# Sheet1.net
KiCad netlist of a schematic drawn in Altium Designer
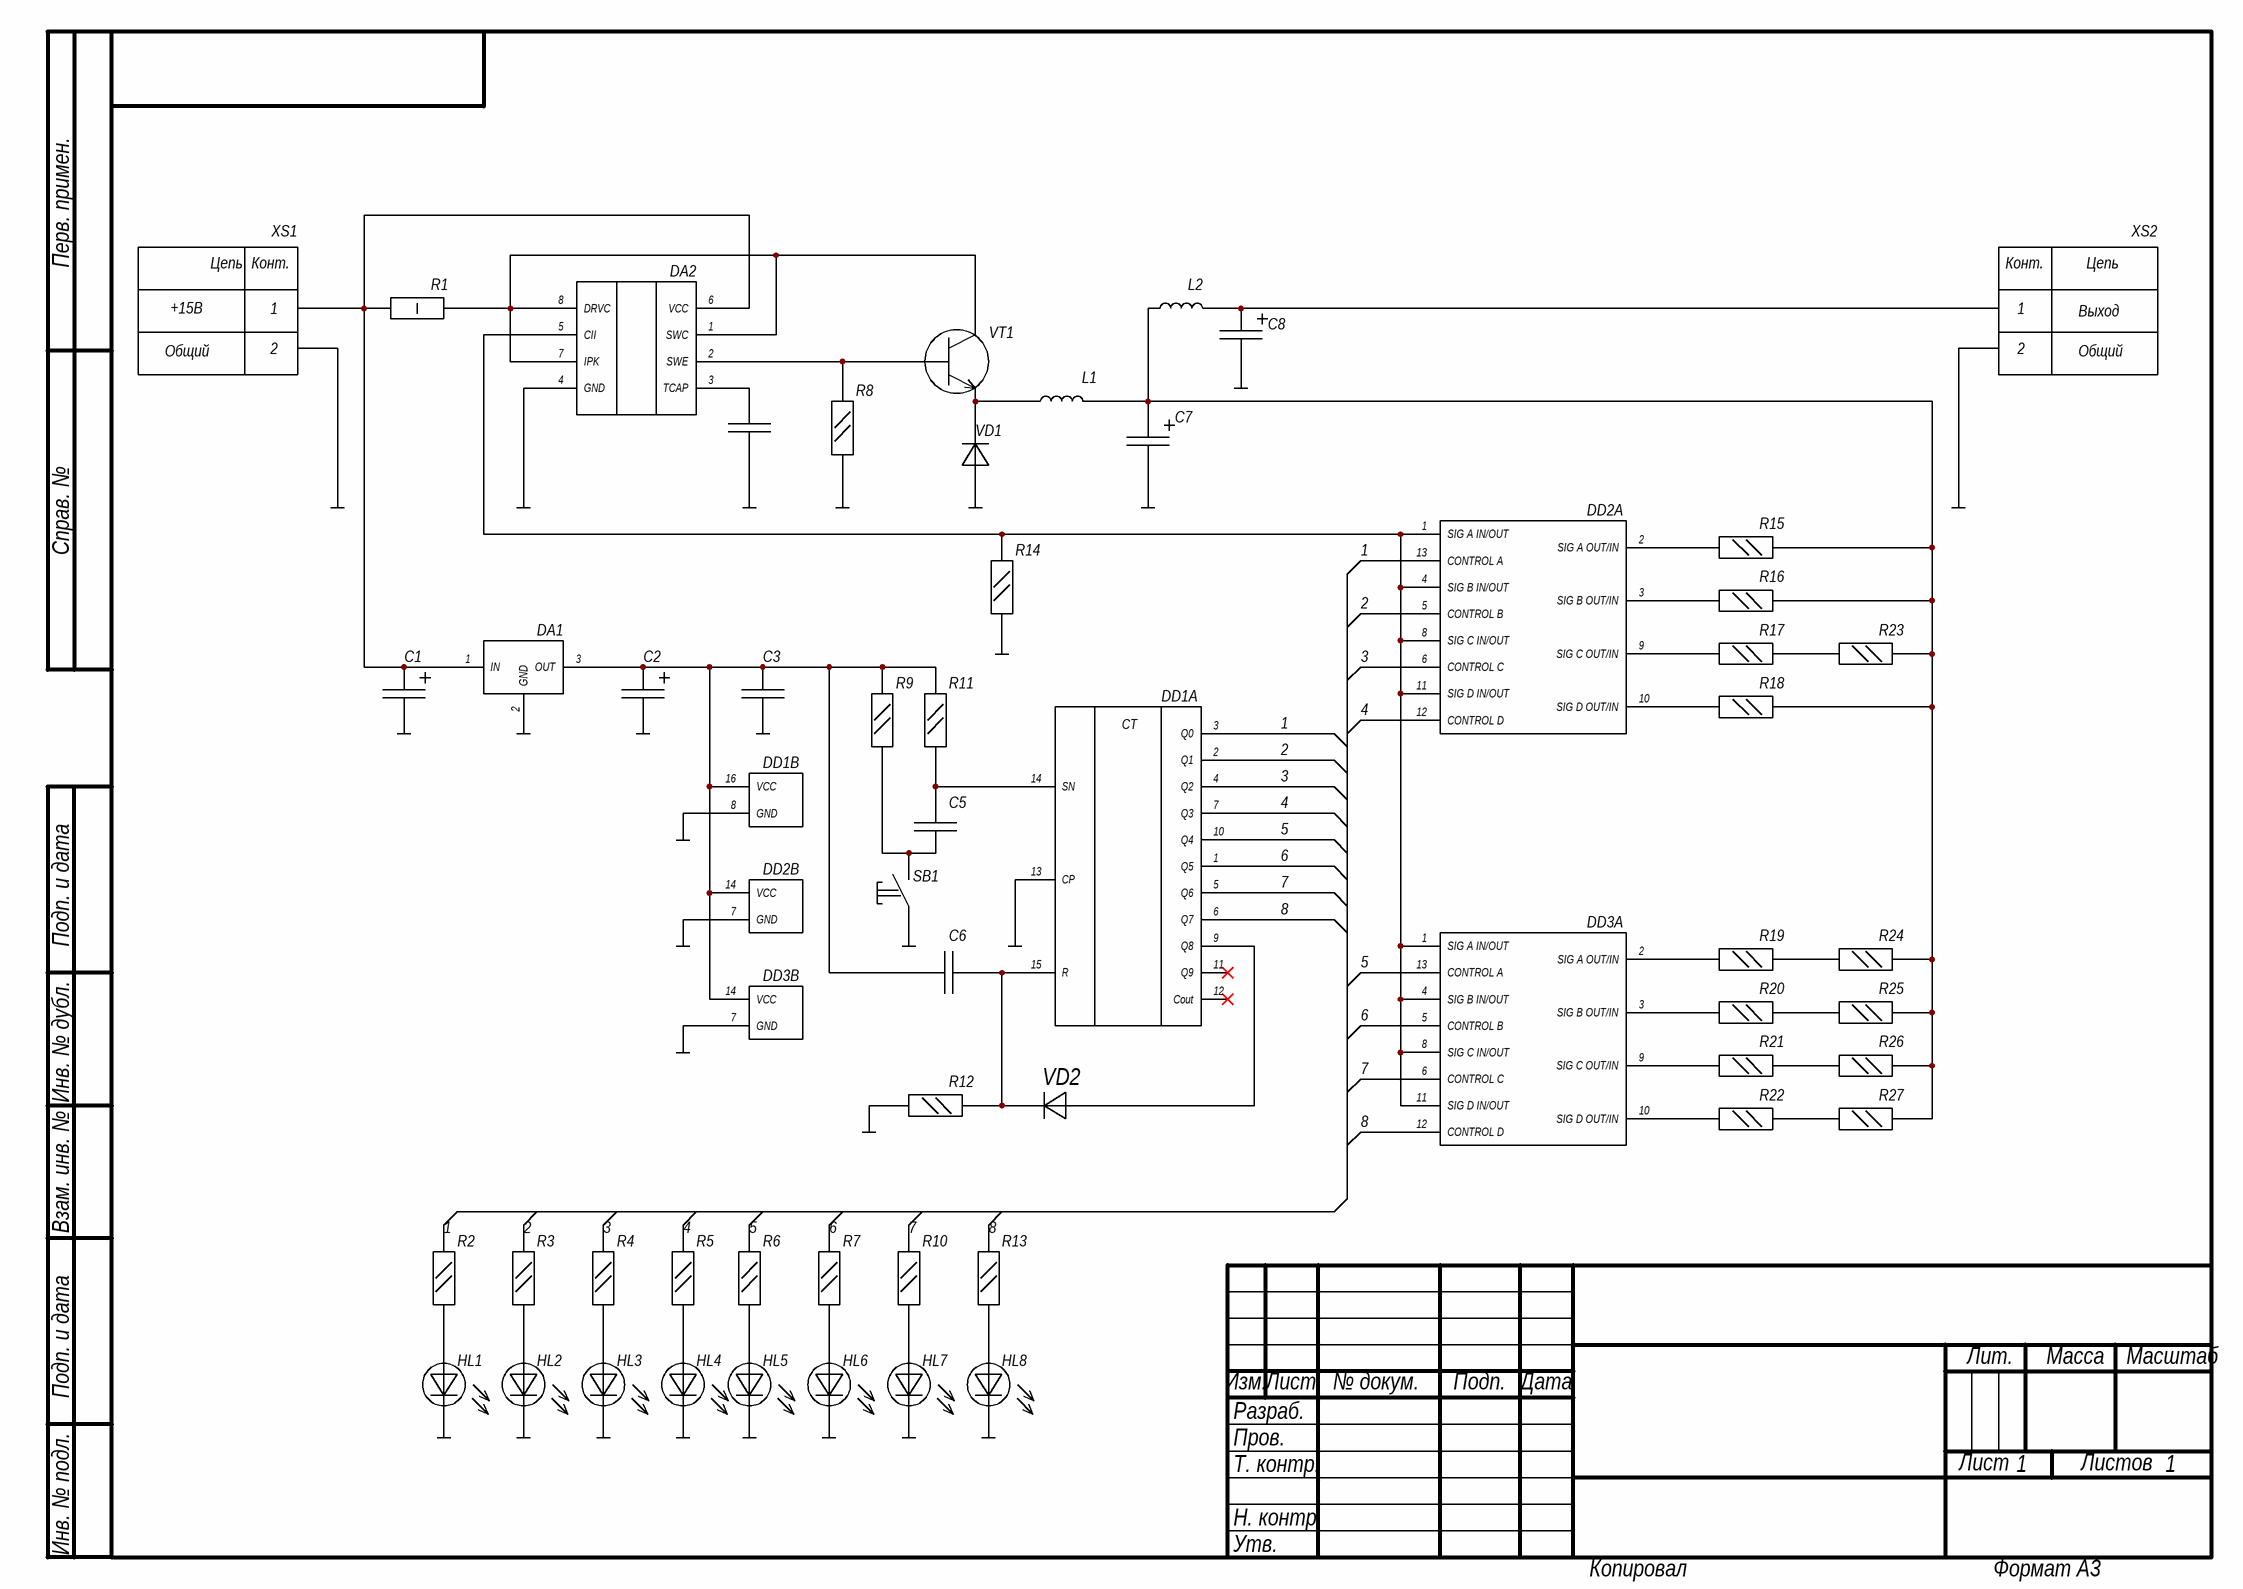
[diagram p0: Sheet1.SchDoc]

(export (version "E")
  (design (tool "Eeschema 10.0.6"))
  (components
    (comp (ref "C1")
      (value "100uF 25V")
      (footprint "CAPPR250-630X1120")
      (description "ECAP TKR101M1EE11 25В 100мкФ ±5% (Jamicon, Китай)")
      (libsource (lib "Schlib1") (part "Cap Polarity 100uF 25V"))
    )
    (comp (ref "C2")
      (value "100uF 25V")
      (footprint "CAPPR250-630X1120")
      (description "ECAP TKR101M1EE11 25В 100мкФ ±5% (Jamicon, Китай)")
      (libsource (lib "Schlib1") (part "Cap Polarity 100uF 25V"))
    )
    (comp (ref "C3")
      (value "Cap Ceramic 0.1uF")
      (footprint "CAPPRB508-450X850")
      (description "CAP X7R RDER71H104K 25В 0.1мкФ ±10% (Murata, Япония)")
      (libsource (lib "Schlib1") (part "Cap Ceramic 0.1uF"))
    )
    (comp (ref "C4")
      (value "Cap Ceramic 470pF")
      (footprint "CAPPRB508-450X850")
      (description "CAP NPO RDE5C1H471J 25В 470пкФ ±5% (Murata, Япония)")
      (libsource (lib "Schlib1") (part "Cap Ceramic 470pF"))
    )
    (comp (ref "C5")
      (value "Cap Ceramic 0.1uF")
      (footprint "CAPPRB508-450X850")
      (description "CAP X7R RDER71H104K 25В 0.1мкФ ±10% (Murata, Япония)")
      (libsource (lib "Schlib1") (part "Cap Ceramic 0.1uF"))
    )
    (comp (ref "C6")
      (value "Cap Ceramic 0.1uF")
      (footprint "CAPPRB508-450X850")
      (description "CAP X7R RDER71H104K 25В 0.1мкФ ±10% (Murata, Япония)")
      (libsource (lib "Schlib1") (part "Cap Ceramic 0.1uF"))
    )
    (comp (ref "C7")
      (value "470uF 25V")
      (footprint "CAPPR350-850X1300")
      (description "ECAP TKR471M1EF14 25В 470мкФ ±5% (Jamicon, Китай)")
      (libsource (lib "Schlib1") (part "Cap Polarity 470uF 25V"))
    )
    (comp (ref "C8")
      (value "470uF 25V")
      (footprint "CAPPR350-850X1300")
      (description "ECAP TKR471M1EF14 25В 470мкФ ±5% (Jamicon, Китай)")
      (libsource (lib "Schlib1") (part "Cap Polarity 470uF 25V"))
    )
    (comp (ref "DA1")
      (value "L7809ABV")
      (footprint "TO-220AB")
      (description "L7809ABV (STMicroelectronics, Швейцария)")
      (libsource (lib "Schlib1") (part "L7809ABV"))
    )
    (comp (ref "DA2")
      (value "MC34063ABN")
      (footprint "DIPS8-300")
      (description "MC34063ABN (STMicroelectronis, Швейцария)")
      (libsource (lib "Schlib1") (part "MC34063ABN"))
    )
    (comp (ref "DD1")
      (value "CD4017BE")
      (footprint "DIPS16-300")
      (description "CD4017BE (Texas Instuments, США)")
      (libsource (lib "Schlib1") (part "CD4017BE"))
    )
    (comp (ref "DD2")
      (value "CD4066BE")
      (footprint "DIPS14-300")
      (description "CD4066BE (HGSEMI, Китай)")
      (libsource (lib "Schlib1") (part "CD4066BE"))
    )
    (comp (ref "DD3")
      (value "CD4066BE")
      (footprint "DIPS14-300")
      (description "CD4066BE (HGSEMI, Китай)")
      (libsource (lib "Schlib1") (part "CD4066BE"))
    )
    (comp (ref "HL1")
      (value "LED Red")
      (footprint "LD-5mm-R")
      (description "GNL-5012ED (G-nor Electronics, Китай)")
      (libsource (lib "Schlib1") (part "LED Red"))
    )
    (comp (ref "HL2")
      (value "LED Red")
      (footprint "LD-5mm-R")
      (description "GNL-5012ED (G-nor Electronics, Китай)")
      (libsource (lib "Schlib1") (part "LED Red"))
    )
    (comp (ref "HL3")
      (value "LED Red")
      (footprint "LD-5mm-R")
      (description "GNL-5012ED (G-nor Electronics, Китай)")
      (libsource (lib "Schlib1") (part "LED Red"))
    )
    (comp (ref "HL4")
      (value "LED Red")
      (footprint "LD-5mm-R")
      (description "GNL-5012ED (G-nor Electronics, Китай)")
      (libsource (lib "Schlib1") (part "LED Red"))
    )
    (comp (ref "HL5")
      (value "LED Red")
      (footprint "LD-5mm-R")
      (description "GNL-5012ED (G-nor Electronics, Китай)")
      (libsource (lib "Schlib1") (part "LED Red"))
    )
    (comp (ref "HL6")
      (value "LED Red")
      (footprint "LD-5mm-R")
      (description "GNL-5012ED (G-nor Electronics, Китай)")
      (libsource (lib "Schlib1") (part "LED Red"))
    )
    (comp (ref "HL7")
      (value "LED Red")
      (footprint "LD-5mm-R")
      (description "GNL-5012ED (G-nor Electronics, Китай)")
      (libsource (lib "Schlib1") (part "LED Red"))
    )
    (comp (ref "HL8")
      (value "LED Red")
      (footprint "LD-5mm-R")
      (description "GNL-5012ED (G-nor Electronics, Китай)")
      (libsource (lib "Schlib1") (part "LED Red"))
    )
    (comp (ref "L1")
      (value "КИ (КИГ) 3,0−100мкГн ±5%")
      (footprint "INDRD_WURTH_WE-TI")
      (description "КИ (КИГ) 3,0−100мкГн ±10% (Россия)")
      (libsource (lib "Schlib1") (part "Inductor КИ (КИГ) 3,0−100мкГн ±5%"))
    )
    (comp (ref "L2")
      (value "КИ (КИГ) 3,0−100мкГн ±5%")
      (footprint "INDRD_WURTH_WE-TI")
      (description "КИ (КИГ) 3,0−100мкГн ±10% (Россия)")
      (libsource (lib "Schlib1") (part "Inductor КИ (КИГ) 3,0−100мкГн ±5%"))
    )
    (comp (ref "R1")
      (value "0,1Ом")
      (footprint "Res 1W")
      (description "С1-4−1−0,1Ом ±5% (Россия)")
      (libsource (lib "Schlib1") (part "Res 0,1 1W"))
    )
    (comp (ref "R2")
      (value "1кОм")
      (footprint "Res 0.125W")
      (description "С1-4−0,125−1кОм ±5% (Россия)")
      (libsource (lib "Schlib1") (part "Res 1K 0.125W"))
    )
    (comp (ref "R3")
      (value "1кОм")
      (footprint "Res 0.125W")
      (description "С1-4−0,125−1кОм ±5% (Россия)")
      (libsource (lib "Schlib1") (part "Res 1K 0.125W"))
    )
    (comp (ref "R4")
      (value "1кОм")
      (footprint "Res 0.125W")
      (description "С1-4−0,125−1кОм ±5% (Россия)")
      (libsource (lib "Schlib1") (part "Res 1K 0.125W"))
    )
    (comp (ref "R5")
      (value "1кОм")
      (footprint "Res 0.125W")
      (description "С1-4−0,125−1кОм ±5% (Россия)")
      (libsource (lib "Schlib1") (part "Res 1K 0.125W"))
    )
    (comp (ref "R6")
      (value "1кОм")
      (footprint "Res 0.125W")
      (description "С1-4−0,125−1кОм ±5% (Россия)")
      (libsource (lib "Schlib1") (part "Res 1K 0.125W"))
    )
    (comp (ref "R7")
      (value "1кОм")
      (footprint "Res 0.125W")
      (description "С1-4−0,125−1кОм ±5% (Россия)")
      (libsource (lib "Schlib1") (part "Res 1K 0.125W"))
    )
    (comp (ref "R8")
      (value "22кОм")
      (footprint "Res 0.125W")
      (description "С1-4−0,125−22кОм ±5% (Россия)")
      (libsource (lib "Schlib1") (part "Res 22K 0.125W"))
    )
    (comp (ref "R9")
      (value "100кОм")
      (footprint "Res 0.125W")
      (description "С1-4−0,125−100кОм ±5% (Россия)")
      (libsource (lib "Schlib1") (part "Res 100K 0.125W"))
    )
    (comp (ref "R10")
      (value "1кОм")
      (footprint "Res 0.125W")
      (description "С1-4−0,125−1кОм ±5% (Россия)")
      (libsource (lib "Schlib1") (part "Res 1K 0.125W"))
    )
    (comp (ref "R11")
      (value "100кОм")
      (footprint "Res 0.125W")
      (description "С1-4−0,125−100кОм ±5% (Россия)")
      (libsource (lib "Schlib1") (part "Res 100K 0.125W"))
    )
    (comp (ref "R12")
      (value "100кОм")
      (footprint "Res 0.125W")
      (description "С1-4−0,125−100кОм ±5% (Россия)")
      (libsource (lib "Schlib1") (part "Res 100K 0.125W"))
    )
    (comp (ref "R13")
      (value "1кОм")
      (footprint "Res 0.125W")
      (description "С1-4−0,125−1кОм ±5% (Россия)")
      (libsource (lib "Schlib1") (part "Res 1K 0.125W"))
    )
    (comp (ref "R14")
      (value "1кОм")
      (footprint "Res 0.125W")
      (description "С1-4−0,125−1,5кОм ±5% (Россия)")
      (libsource (lib "Schlib1") (part "Res 1,5K 0.125W"))
    )
    (comp (ref "R15")
      (value "270Ом")
      (footprint "Res 0.125W")
      (description "С1-4−0,125−270Ом ±5% (Россия)")
      (libsource (lib "Schlib1") (part "Res 270 0.125W"))
    )
    (comp (ref "R16")
      (value "1кОм")
      (footprint "Res 0.125W")
      (description "С1-4−0,125−1,5кОм ±5% (Россия)")
      (libsource (lib "Schlib1") (part "Res 1,5K 0.125W"))
    )
    (comp (ref "R17")
      (value "2кОм")
      (footprint "Res 0.125W")
      (description "С1-4−0,125−2кОм ±5% (Россия)")
      (libsource (lib "Schlib1") (part "Res 2K 0.125W"))
    )
    (comp (ref "R18")
      (value "3,9кОм")
      (footprint "Res 0.125W")
      (description "С1-4−0,125−3,9кОм ±5% (Россия)")
      (libsource (lib "Schlib1") (part "Res 3,9K 0.125W"))
    )
    (comp (ref "R19")
      (value "4,3кОм")
      (footprint "Res 0.125W")
      (description "С1-4−0,125−4,3кОм ±5% (Россия)")
      (libsource (lib "Schlib1") (part "Res 4,3K 0.125W"))
    )
    (comp (ref "R20")
      (value "5,6кОм")
      (footprint "Res 0.125W")
      (description "С1-4−0,125−5,6кОм ±5% (Россия)")
      (libsource (lib "Schlib1") (part "Res 5,6K 0.125W"))
    )
    (comp (ref "R21")
      (value "7,5кОм")
      (footprint "Res 0.125W")
      (description "С1-4−0,125−7,5кОм ±5% (Россия)")
      (libsource (lib "Schlib1") (part "Res 7,5K 0.125W"))
    )
    (comp (ref "R22")
      (value "9,1кОм")
      (footprint "Res 0.125W")
      (description "С1-4−0,125−9,1кОм ±5% (Россия)")
      (libsource (lib "Schlib1") (part "Res 9,1K 0.125W"))
    )
    (comp (ref "R23")
      (value "100Ом")
      (footprint "Res 0.125W")
      (description "С1-4−0,125−100Ом ±5% (Россия)")
      (libsource (lib "Schlib1") (part "Res 100 0.125W"))
    )
    (comp (ref "R24")
      (value "200Ом")
      (footprint "Res 0.125W")
      (description "С1-4−0,125−200Ом ±5% (Россия)")
      (libsource (lib "Schlib1") (part "Res 200 0.125W"))
    )
    (comp (ref "R25")
      (value "200Ом")
      (footprint "Res 0.125W")
      (description "С1-4−0,125−200Ом ±5% (Россия)")
      (libsource (lib "Schlib1") (part "Res 200 0.125W"))
    )
    (comp (ref "R26")
      (value "100Ом")
      (footprint "Res 0.125W")
      (description "С1-4−0,125−100Ом ±5% (Россия)")
      (libsource (lib "Schlib1") (part "Res 100 0.125W"))
    )
    (comp (ref "R27")
      (value "300Ом")
      (footprint "Res 0.125W")
      (description "С1-4−0,125−300Ом ±5% (Россия)")
      (libsource (lib "Schlib1") (part "Res 300 0.125W"))
    )
    (comp (ref "SB1")
      (value "Button SMD")
      (footprint "Button SMD")
      (description "Кнопка тактовая 1437566-3 (TE Connectivity, США)")
      (libsource (lib "Schlib1") (part "Button"))
    )
    (comp (ref "VD1")
      (value "1N5820")
      (footprint "DO-27")
      (description "1N5820 (Diotec, Германия)")
      (libsource (lib "Schlib1") (part "Diode 1N5820"))
    )
    (comp (ref "VD2")
      (value "1N4002")
      (footprint "DO-35")
      (description "1N4148 (Diotec, Германия)")
      (fields (field (name "PUBLISHER") "Andrew Danich"))
      (libsource (lib "Schlib1") (part "Diode 1N4148"))
    )
    (comp (ref "VT1")
      (value "TIP121G")
      (footprint "TO-220AB")
      (description "TIP121G (ON Semiconductor, США)")
      (libsource (lib "Schlib1") (part "Transistor TIP121G"))
    )
    (comp (ref "XS1")
      (value "Power Connector 2 pin")
      (footprint "WIELAND_25.161.0253.0")
      (description "25.161.0253.0 (Wieland Electric, Германия)")
      (libsource (lib "Schlib1") (part "Power Connector 2 pin"))
    )
    (comp (ref "XS2")
      (value "Power Connector 2 pin")
      (footprint "WIELAND_25.161.0253.0")
      (description "25.161.0253.0 (Wieland Electric, Германия)")
      (libsource (lib "Schlib1") (part "Power Connector 2 pin"))
    )
  )
  (nets
    (net (code "1") (name "/1") (class "Default")
      (node (ref "DD1") (pin "3") (pinfunction "Q0_3") (pintype "passive"))
      (node (ref "DD2") (pin "13") (pinfunction "CONTROL_A_13") (pintype "passive"))
    )
    (net (code "2") (name "/2") (class "Default")
      (node (ref "DD1") (pin "2") (pinfunction "Q1_2") (pintype "passive"))
      (node (ref "DD2") (pin "5") (pinfunction "CONTROL_B_5") (pintype "passive"))
    )
    (net (code "3") (name "/3") (class "Default")
      (node (ref "DD1") (pin "4") (pinfunction "Q2_4") (pintype "passive"))
      (node (ref "DD2") (pin "6") (pinfunction "CONTROL_C_6") (pintype "passive"))
    )
    (net (code "4") (name "/4") (class "Default")
      (node (ref "DD1") (pin "7") (pinfunction "Q3_7") (pintype "passive"))
      (node (ref "DD2") (pin "12") (pinfunction "CONTROL_D_12") (pintype "passive"))
    )
    (net (code "5") (name "/5") (class "Default")
      (node (ref "DD1") (pin "10") (pinfunction "Q4_10") (pintype "passive"))
      (node (ref "DD3") (pin "13") (pinfunction "CONTROL_A_13") (pintype "passive"))
    )
    (net (code "6") (name "/6") (class "Default")
      (node (ref "DD1") (pin "1") (pinfunction "Q5_1") (pintype "passive"))
      (node (ref "DD3") (pin "5") (pinfunction "CONTROL_B_5") (pintype "passive"))
    )
    (net (code "7") (name "/7") (class "Default")
      (node (ref "DD1") (pin "5") (pinfunction "Q6_5") (pintype "passive"))
      (node (ref "DD3") (pin "6") (pinfunction "CONTROL_C_6") (pintype "passive"))
    )
    (net (code "8") (name "/8") (class "Default")
      (node (ref "DD1") (pin "6") (pinfunction "Q7_6") (pintype "passive"))
      (node (ref "DD3") (pin "12") (pinfunction "CONTROL_D_12") (pintype "passive"))
    )
    (net (code "9") (name "GND") (class "Default")
      (node (ref "C1") (pin "2") (pinfunction "2_2") (pintype "passive"))
      (node (ref "C2") (pin "2") (pinfunction "2_2") (pintype "passive"))
      (node (ref "C3") (pin "2") (pinfunction "2_2") (pintype "passive"))
      (node (ref "C4") (pin "2") (pinfunction "2_2") (pintype "passive"))
      (node (ref "C7") (pin "2") (pinfunction "2_2") (pintype "passive"))
      (node (ref "C8") (pin "2") (pinfunction "2_2") (pintype "passive"))
      (node (ref "DA1") (pin "2") (pinfunction "GND_2") (pintype "passive"))
      (node (ref "DA2") (pin "4") (pinfunction "GND_4") (pintype "passive"))
      (node (ref "DD1") (pin "13") (pinfunction "CP_13") (pintype "passive"))
      (node (ref "DD1") (pin "8") (pinfunction "GND_8") (pintype "passive"))
      (node (ref "DD2") (pin "7") (pinfunction "GND_7") (pintype "passive"))
      (node (ref "DD3") (pin "7") (pinfunction "GND_7") (pintype "passive"))
      (node (ref "HL1") (pin "2") (pinfunction "K_2") (pintype "passive"))
      (node (ref "HL2") (pin "2") (pinfunction "K_2") (pintype "passive"))
      (node (ref "HL3") (pin "2") (pinfunction "K_2") (pintype "passive"))
      (node (ref "HL4") (pin "2") (pinfunction "K_2") (pintype "passive"))
      (node (ref "HL5") (pin "2") (pinfunction "K_2") (pintype "passive"))
      (node (ref "HL6") (pin "2") (pinfunction "K_2") (pintype "passive"))
      (node (ref "HL7") (pin "2") (pinfunction "K_2") (pintype "passive"))
      (node (ref "HL8") (pin "2") (pinfunction "K_2") (pintype "passive"))
      (node (ref "R12") (pin "1") (pinfunction "1_1") (pintype "passive"))
      (node (ref "R14") (pin "1") (pinfunction "1_1") (pintype "passive"))
      (node (ref "R8") (pin "1") (pinfunction "1_1") (pintype "passive"))
      (node (ref "SB1") (pin "1") (pintype "passive"))
      (node (ref "VD1") (pin "1") (pinfunction "А_1") (pintype "passive"))
      (node (ref "XS1") (pin "2") (pinfunction "2_2") (pintype "passive"))
      (node (ref "XS2") (pin "2") (pinfunction "2_2") (pintype "passive"))
    )
    (net (code "10") (name "Net-(C5-Pad2)") (class "Default")
      (node (ref "C5") (pin "2") (pinfunction "2_2") (pintype "passive"))
      (node (ref "R9") (pin "1") (pinfunction "1_1") (pintype "passive"))
      (node (ref "SB1") (pin "2") (pintype "passive"))
    )
    (net (code "11") (name "Net-(C7-Pad1)") (class "Default")
      (node (ref "C7") (pin "1") (pinfunction "1_1") (pintype "passive"))
      (node (ref "L1") (pin "2") (pinfunction "2_2") (pintype "passive"))
      (node (ref "L2") (pin "1") (pinfunction "1_1") (pintype "passive"))
      (node (ref "R15") (pin "2") (pinfunction "2_2") (pintype "passive"))
      (node (ref "R16") (pin "2") (pinfunction "2_2") (pintype "passive"))
      (node (ref "R18") (pin "2") (pinfunction "2_2") (pintype "passive"))
      (node (ref "R23") (pin "2") (pinfunction "2_2") (pintype "passive"))
      (node (ref "R24") (pin "2") (pinfunction "2_2") (pintype "passive"))
      (node (ref "R25") (pin "2") (pinfunction "2_2") (pintype "passive"))
      (node (ref "R26") (pin "2") (pinfunction "2_2") (pintype "passive"))
      (node (ref "R27") (pin "2") (pinfunction "2_2") (pintype "passive"))
    )
    (net (code "12") (name "Net-(C8-Pad1)") (class "Default")
      (node (ref "C8") (pin "1") (pinfunction "1_1") (pintype "passive"))
      (node (ref "L2") (pin "2") (pinfunction "2_2") (pintype "passive"))
      (node (ref "XS2") (pin "1") (pinfunction "1_1") (pintype "passive"))
    )
    (net (code "13") (name "Net-(DA1-IN)") (class "Default")
      (node (ref "C1") (pin "1") (pinfunction "1_1") (pintype "passive"))
      (node (ref "DA1") (pin "1") (pinfunction "IN_1") (pintype "passive"))
      (node (ref "DA2") (pin "6") (pinfunction "VCC_6") (pintype "passive"))
      (node (ref "R1") (pin "2") (pinfunction "2_2") (pintype "passive"))
      (node (ref "XS1") (pin "1") (pinfunction "1_1") (pintype "passive"))
    )
    (net (code "14") (name "Net-(DA1-OUT)") (class "Default")
      (node (ref "C2") (pin "1") (pinfunction "1_1") (pintype "passive"))
      (node (ref "C3") (pin "1") (pinfunction "1_1") (pintype "passive"))
      (node (ref "C6") (pin "1") (pinfunction "1_1") (pintype "passive"))
      (node (ref "DA1") (pin "3") (pinfunction "OUT_3") (pintype "passive"))
      (node (ref "DD1") (pin "16") (pinfunction "VCC_16") (pintype "passive"))
      (node (ref "DD2") (pin "14") (pinfunction "VCC_14") (pintype "passive"))
      (node (ref "DD3") (pin "14") (pinfunction "VCC_14") (pintype "passive"))
      (node (ref "R11") (pin "2") (pinfunction "2_2") (pintype "passive"))
      (node (ref "R9") (pin "2") (pinfunction "2_2") (pintype "passive"))
    )
    (net (code "15") (name "Net-(DA2-CII)") (class "Default")
      (node (ref "DA2") (pin "5") (pinfunction "CII_5") (pintype "passive"))
      (node (ref "DD2") (pin "1") (pinfunction "SIG_A_IN/OUT_1") (pintype "passive"))
      (node (ref "DD2") (pin "11") (pinfunction "SIG_D_IN/OUT_11") (pintype "passive"))
      (node (ref "DD2") (pin "4") (pinfunction "SIG_B_IN/OUT_4") (pintype "passive"))
      (node (ref "DD2") (pin "8") (pinfunction "SIG_C_IN/OUT_8") (pintype "passive"))
      (node (ref "DD3") (pin "1") (pinfunction "SIG_A_IN/OUT_1") (pintype "passive"))
      (node (ref "DD3") (pin "11") (pinfunction "SIG_D_IN/OUT_11") (pintype "passive"))
      (node (ref "DD3") (pin "4") (pinfunction "SIG_B_IN/OUT_4") (pintype "passive"))
      (node (ref "DD3") (pin "8") (pinfunction "SIG_C_IN/OUT_8") (pintype "passive"))
      (node (ref "R14") (pin "2") (pinfunction "2_2") (pintype "passive"))
    )
    (net (code "16") (name "Net-(DA2-DRVC)") (class "Default")
      (node (ref "DA2") (pin "1") (pinfunction "SWC_1") (pintype "passive"))
      (node (ref "DA2") (pin "7") (pinfunction "IPK_7") (pintype "passive"))
      (node (ref "DA2") (pin "8") (pinfunction "DRVC_8") (pintype "passive"))
      (node (ref "R1") (pin "1") (pinfunction "1_1") (pintype "passive"))
      (node (ref "VT1") (pin "2") (pinfunction "К_2") (pintype "passive"))
    )
    (net (code "17") (name "Net-(DA2-SWE)") (class "Default")
      (node (ref "DA2") (pin "2") (pinfunction "SWE_2") (pintype "passive"))
      (node (ref "R8") (pin "2") (pinfunction "2_2") (pintype "passive"))
      (node (ref "VT1") (pin "1") (pinfunction "Б_1") (pintype "passive"))
    )
    (net (code "18") (name "Net-(DA2-TCAP)") (class "Default")
      (node (ref "C4") (pin "1") (pinfunction "1_1") (pintype "passive"))
      (node (ref "DA2") (pin "3") (pinfunction "TCAP_3") (pintype "passive"))
    )
    (net (code "19") (name "Net-(DD1A-Q8)") (class "Default")
      (node (ref "DD1") (pin "9") (pinfunction "Q8_9") (pintype "passive"))
      (node (ref "VD2") (pin "1") (pinfunction "А_1") (pintype "passive"))
    )
    (net (code "20") (name "Net-(DD1A-R)") (class "Default")
      (node (ref "C6") (pin "2") (pinfunction "2_2") (pintype "passive"))
      (node (ref "DD1") (pin "15") (pinfunction "R_15") (pintype "passive"))
      (node (ref "R12") (pin "2") (pinfunction "2_2") (pintype "passive"))
      (node (ref "VD2") (pin "2") (pinfunction "К_2") (pintype "passive"))
    )
    (net (code "21") (name "Net-(DD1A-SN)") (class "Default")
      (node (ref "C5") (pin "1") (pinfunction "1_1") (pintype "passive"))
      (node (ref "DD1") (pin "14") (pinfunction "SN_14") (pintype "passive"))
      (node (ref "R11") (pin "1") (pinfunction "1_1") (pintype "passive"))
    )
    (net (code "22") (name "Net-(DD2A-SIG_A_OUT{slash}IN)") (class "Default")
      (node (ref "DD2") (pin "2") (pinfunction "SIG_A_OUT/IN_2") (pintype "passive"))
      (node (ref "R15") (pin "1") (pinfunction "1_1") (pintype "passive"))
    )
    (net (code "23") (name "Net-(DD2A-SIG_B_OUT{slash}IN)") (class "Default")
      (node (ref "DD2") (pin "3") (pinfunction "SIG_B_OUT/IN_3") (pintype "passive"))
      (node (ref "R16") (pin "1") (pinfunction "1_1") (pintype "passive"))
    )
    (net (code "24") (name "Net-(DD2A-SIG_C_OUT{slash}IN)") (class "Default")
      (node (ref "DD2") (pin "9") (pinfunction "SIG_C_OUT/IN_9") (pintype "passive"))
      (node (ref "R17") (pin "1") (pinfunction "1_1") (pintype "passive"))
    )
    (net (code "25") (name "Net-(DD2A-SIG_D_OUT{slash}IN)") (class "Default")
      (node (ref "DD2") (pin "10") (pinfunction "SIG_D_OUT/IN_10") (pintype "passive"))
      (node (ref "R18") (pin "1") (pinfunction "1_1") (pintype "passive"))
    )
    (net (code "26") (name "Net-(DD3A-SIG_A_OUT{slash}IN)") (class "Default")
      (node (ref "DD3") (pin "2") (pinfunction "SIG_A_OUT/IN_2") (pintype "passive"))
      (node (ref "R19") (pin "1") (pinfunction "1_1") (pintype "passive"))
    )
    (net (code "27") (name "Net-(DD3A-SIG_B_OUT{slash}IN)") (class "Default")
      (node (ref "DD3") (pin "3") (pinfunction "SIG_B_OUT/IN_3") (pintype "passive"))
      (node (ref "R20") (pin "1") (pinfunction "1_1") (pintype "passive"))
    )
    (net (code "28") (name "Net-(DD3A-SIG_C_OUT{slash}IN)") (class "Default")
      (node (ref "DD3") (pin "9") (pinfunction "SIG_C_OUT/IN_9") (pintype "passive"))
      (node (ref "R21") (pin "1") (pinfunction "1_1") (pintype "passive"))
    )
    (net (code "29") (name "Net-(DD3A-SIG_D_OUT{slash}IN)") (class "Default")
      (node (ref "DD3") (pin "10") (pinfunction "SIG_D_OUT/IN_10") (pintype "passive"))
      (node (ref "R22") (pin "1") (pinfunction "1_1") (pintype "passive"))
    )
    (net (code "30") (name "Net-(HL1-A)") (class "Default")
      (node (ref "HL1") (pin "1") (pinfunction "A_1") (pintype "passive"))
      (node (ref "R2") (pin "1") (pinfunction "1_1") (pintype "passive"))
    )
    (net (code "31") (name "Net-(HL2-A)") (class "Default")
      (node (ref "HL2") (pin "1") (pinfunction "A_1") (pintype "passive"))
      (node (ref "R3") (pin "1") (pinfunction "1_1") (pintype "passive"))
    )
    (net (code "32") (name "Net-(HL3-A)") (class "Default")
      (node (ref "HL3") (pin "1") (pinfunction "A_1") (pintype "passive"))
      (node (ref "R4") (pin "1") (pinfunction "1_1") (pintype "passive"))
    )
    (net (code "33") (name "Net-(HL4-A)") (class "Default")
      (node (ref "HL4") (pin "1") (pinfunction "A_1") (pintype "passive"))
      (node (ref "R5") (pin "1") (pinfunction "1_1") (pintype "passive"))
    )
    (net (code "34") (name "Net-(HL5-A)") (class "Default")
      (node (ref "HL5") (pin "1") (pinfunction "A_1") (pintype "passive"))
      (node (ref "R6") (pin "1") (pinfunction "1_1") (pintype "passive"))
    )
    (net (code "35") (name "Net-(HL6-A)") (class "Default")
      (node (ref "HL6") (pin "1") (pinfunction "A_1") (pintype "passive"))
      (node (ref "R7") (pin "1") (pinfunction "1_1") (pintype "passive"))
    )
    (net (code "36") (name "Net-(HL7-A)") (class "Default")
      (node (ref "HL7") (pin "1") (pinfunction "A_1") (pintype "passive"))
      (node (ref "R10") (pin "1") (pinfunction "1_1") (pintype "passive"))
    )
    (net (code "37") (name "Net-(HL8-A)") (class "Default")
      (node (ref "HL8") (pin "1") (pinfunction "A_1") (pintype "passive"))
      (node (ref "R13") (pin "1") (pinfunction "1_1") (pintype "passive"))
    )
    (net (code "38") (name "Net-(R17-Pad2)") (class "Default")
      (node (ref "R17") (pin "2") (pinfunction "2_2") (pintype "passive"))
      (node (ref "R23") (pin "1") (pinfunction "1_1") (pintype "passive"))
    )
    (net (code "39") (name "Net-(R19-Pad2)") (class "Default")
      (node (ref "R19") (pin "2") (pinfunction "2_2") (pintype "passive"))
      (node (ref "R24") (pin "1") (pinfunction "1_1") (pintype "passive"))
    )
    (net (code "40") (name "Net-(R20-Pad2)") (class "Default")
      (node (ref "R20") (pin "2") (pinfunction "2_2") (pintype "passive"))
      (node (ref "R25") (pin "1") (pinfunction "1_1") (pintype "passive"))
    )
    (net (code "41") (name "Net-(R21-Pad2)") (class "Default")
      (node (ref "R21") (pin "2") (pinfunction "2_2") (pintype "passive"))
      (node (ref "R26") (pin "1") (pinfunction "1_1") (pintype "passive"))
    )
    (net (code "42") (name "Net-(R22-Pad2)") (class "Default")
      (node (ref "R22") (pin "2") (pinfunction "2_2") (pintype "passive"))
      (node (ref "R27") (pin "1") (pinfunction "1_1") (pintype "passive"))
    )
    (net (code "43") (name "Net-(VD1-К)") (class "Default")
      (node (ref "L1") (pin "1") (pinfunction "1_1") (pintype "passive"))
      (node (ref "VD1") (pin "2") (pinfunction "К_2") (pintype "passive"))
      (node (ref "VT1") (pin "3") (pinfunction "Э_3") (pintype "passive"))
    )
    (net (code "44") (name "unconnected-(DD1A-Cout-Pad12)") (class "Default")
      (node (ref "DD1") (pin "12") (pinfunction "Cout_12") (pintype "passive+no_connect"))
    )
    (net (code "45") (name "unconnected-(DD1A-Q9-Pad11)") (class "Default")
      (node (ref "DD1") (pin "11") (pinfunction "Q9_11") (pintype "passive+no_connect"))
    )
    (net (code "46") (name "unconnected-(R2-Pad2)") (class "Default")
      (node (ref "R2") (pin "2") (pinfunction "2_2") (pintype "passive"))
    )
    (net (code "47") (name "unconnected-(R3-Pad2)") (class "Default")
      (node (ref "R3") (pin "2") (pinfunction "2_2") (pintype "passive"))
    )
    (net (code "48") (name "unconnected-(R4-Pad2)") (class "Default")
      (node (ref "R4") (pin "2") (pinfunction "2_2") (pintype "passive"))
    )
    (net (code "49") (name "unconnected-(R5-Pad2)") (class "Default")
      (node (ref "R5") (pin "2") (pinfunction "2_2") (pintype "passive"))
    )
    (net (code "50") (name "unconnected-(R6-Pad2)") (class "Default")
      (node (ref "R6") (pin "2") (pinfunction "2_2") (pintype "passive"))
    )
    (net (code "51") (name "unconnected-(R7-Pad2)") (class "Default")
      (node (ref "R7") (pin "2") (pinfunction "2_2") (pintype "passive"))
    )
    (net (code "52") (name "unconnected-(R10-Pad2)") (class "Default")
      (node (ref "R10") (pin "2") (pinfunction "2_2") (pintype "passive"))
    )
    (net (code "53") (name "unconnected-(R13-Pad2)") (class "Default")
      (node (ref "R13") (pin "2") (pinfunction "2_2") (pintype "passive"))
    )
  )
)
